# CrossPort.net
KiCad netlist of a schematic drawn in Altium Designer
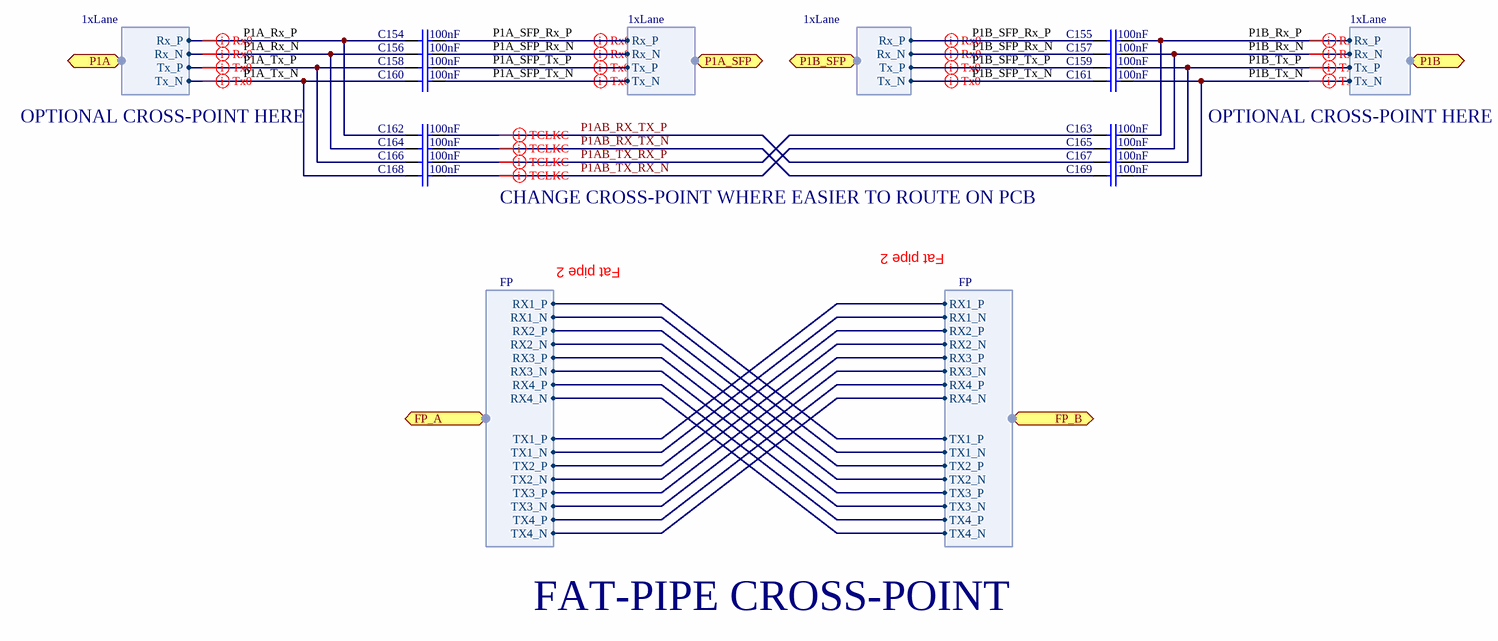
[diagram p0: CrossPort.SchDoc]

(export (version "E")
  (design (tool "Eeschema 10.0.6"))
  (components
    (comp (ref "C154")
      (value "100nF")
      (footprint "CAPC0603X33N")
      (description "Non-polarised capacitor")
      (fields
        (field (name "PART NUMBER") "CC0201_100NF_6.3V_10%_X5R")
        (field (name "VOLTAGE") "6.3V")
        (field (name "AUTHOR") "CERN DEM JLC")
      )
      (libsource (lib "Capacitors") (part "Capacitor - non polarized"))
    )
    (comp (ref "C155")
      (value "100nF")
      (footprint "CAPC0603X33N")
      (description "Non-polarised capacitor")
      (fields
        (field (name "PART NUMBER") "CC0201_100NF_6.3V_10%_X5R")
        (field (name "VOLTAGE") "6.3V")
        (field (name "AUTHOR") "CERN DEM JLC")
      )
      (libsource (lib "Capacitors") (part "Capacitor - non polarized"))
    )
    (comp (ref "C156")
      (value "100nF")
      (footprint "CAPC0603X33N")
      (description "Non-polarised capacitor")
      (fields
        (field (name "PART NUMBER") "CC0201_100NF_6.3V_10%_X5R")
        (field (name "VOLTAGE") "6.3V")
        (field (name "AUTHOR") "CERN DEM JLC")
      )
      (libsource (lib "Capacitors") (part "Capacitor - non polarized"))
    )
    (comp (ref "C157")
      (value "100nF")
      (footprint "CAPC0603X33N")
      (description "Non-polarised capacitor")
      (fields
        (field (name "PART NUMBER") "CC0201_100NF_6.3V_10%_X5R")
        (field (name "VOLTAGE") "6.3V")
        (field (name "AUTHOR") "CERN DEM JLC")
      )
      (libsource (lib "Capacitors") (part "Capacitor - non polarized"))
    )
    (comp (ref "C158")
      (value "100nF")
      (footprint "CAPC0603X33N")
      (description "Non-polarised capacitor")
      (fields
        (field (name "PART NUMBER") "CC0201_100NF_6.3V_10%_X5R")
        (field (name "VOLTAGE") "6.3V")
        (field (name "AUTHOR") "CERN DEM JLC")
      )
      (libsource (lib "Capacitors") (part "Capacitor - non polarized"))
    )
    (comp (ref "C159")
      (value "100nF")
      (footprint "CAPC0603X33N")
      (description "Non-polarised capacitor")
      (fields
        (field (name "PART NUMBER") "CC0201_100NF_6.3V_10%_X5R")
        (field (name "VOLTAGE") "6.3V")
        (field (name "AUTHOR") "CERN DEM JLC")
      )
      (libsource (lib "Capacitors") (part "Capacitor - non polarized"))
    )
    (comp (ref "C160")
      (value "100nF")
      (footprint "CAPC0603X33N")
      (description "Non-polarised capacitor")
      (fields
        (field (name "PART NUMBER") "CC0201_100NF_6.3V_10%_X5R")
        (field (name "VOLTAGE") "6.3V")
        (field (name "AUTHOR") "CERN DEM JLC")
      )
      (libsource (lib "Capacitors") (part "Capacitor - non polarized"))
    )
    (comp (ref "C161")
      (value "100nF")
      (footprint "CAPC0603X33N")
      (description "Non-polarised capacitor")
      (fields
        (field (name "PART NUMBER") "CC0201_100NF_6.3V_10%_X5R")
        (field (name "VOLTAGE") "6.3V")
        (field (name "AUTHOR") "CERN DEM JLC")
      )
      (libsource (lib "Capacitors") (part "Capacitor - non polarized"))
    )
    (comp (ref "C162")
      (value "100nF")
      (footprint "CAPC0603X33N")
      (description "Non-polarised capacitor")
      (fields
        (field (name "PART NUMBER") "CC0201_100NF_6.3V_10%_X5R")
        (field (name "VOLTAGE") "6.3V")
        (field (name "AUTHOR") "CERN DEM JLC")
      )
      (libsource (lib "Capacitors") (part "Capacitor - non polarized"))
    )
    (comp (ref "C163")
      (value "100nF")
      (footprint "CAPC0603X33N")
      (description "Non-polarised capacitor")
      (fields
        (field (name "PART NUMBER") "CC0201_100NF_6.3V_10%_X5R")
        (field (name "VOLTAGE") "6.3V")
        (field (name "AUTHOR") "CERN DEM JLC")
      )
      (libsource (lib "Capacitors") (part "Capacitor - non polarized"))
    )
    (comp (ref "C164")
      (value "100nF")
      (footprint "CAPC0603X33N")
      (description "Non-polarised capacitor")
      (fields
        (field (name "PART NUMBER") "CC0201_100NF_6.3V_10%_X5R")
        (field (name "VOLTAGE") "6.3V")
        (field (name "AUTHOR") "CERN DEM JLC")
      )
      (libsource (lib "Capacitors") (part "Capacitor - non polarized"))
    )
    (comp (ref "C165")
      (value "100nF")
      (footprint "CAPC0603X33N")
      (description "Non-polarised capacitor")
      (fields
        (field (name "PART NUMBER") "CC0201_100NF_6.3V_10%_X5R")
        (field (name "VOLTAGE") "6.3V")
        (field (name "AUTHOR") "CERN DEM JLC")
      )
      (libsource (lib "Capacitors") (part "Capacitor - non polarized"))
    )
    (comp (ref "C166")
      (value "100nF")
      (footprint "CAPC0603X33N")
      (description "Non-polarised capacitor")
      (fields
        (field (name "PART NUMBER") "CC0201_100NF_6.3V_10%_X5R")
        (field (name "VOLTAGE") "6.3V")
        (field (name "AUTHOR") "CERN DEM JLC")
      )
      (libsource (lib "Capacitors") (part "Capacitor - non polarized"))
    )
    (comp (ref "C167")
      (value "100nF")
      (footprint "CAPC0603X33N")
      (description "Non-polarised capacitor")
      (fields
        (field (name "PART NUMBER") "CC0201_100NF_6.3V_10%_X5R")
        (field (name "VOLTAGE") "6.3V")
        (field (name "AUTHOR") "CERN DEM JLC")
      )
      (libsource (lib "Capacitors") (part "Capacitor - non polarized"))
    )
    (comp (ref "C168")
      (value "100nF")
      (footprint "CAPC0603X33N")
      (description "Non-polarised capacitor")
      (fields
        (field (name "PART NUMBER") "CC0201_100NF_6.3V_10%_X5R")
        (field (name "VOLTAGE") "6.3V")
        (field (name "AUTHOR") "CERN DEM JLC")
      )
      (libsource (lib "Capacitors") (part "Capacitor - non polarized"))
    )
    (comp (ref "C169")
      (value "100nF")
      (footprint "CAPC0603X33N")
      (description "Non-polarised capacitor")
      (fields
        (field (name "PART NUMBER") "CC0201_100NF_6.3V_10%_X5R")
        (field (name "VOLTAGE") "6.3V")
        (field (name "AUTHOR") "CERN DEM JLC")
      )
      (libsource (lib "Capacitors") (part "Capacitor - non polarized"))
    )
  )
  (nets
    (net (code "3") (name "/P1AB_RX_TX_N") (class "Default")
      (node (ref "C164") (pin "1") (pinfunction "1_1") (pintype "passive"))
      (node (ref "C169") (pin "2") (pinfunction "2_2") (pintype "passive"))
    )
    (net (code "4") (name "/P1AB_RX_TX_P") (class "Default")
      (node (ref "C162") (pin "1") (pinfunction "1_1") (pintype "passive"))
      (node (ref "C167") (pin "2") (pinfunction "2_2") (pintype "passive"))
    )
    (net (code "5") (name "/P1AB_TX_RX_N") (class "Default")
      (node (ref "C165") (pin "2") (pinfunction "2_2") (pintype "passive"))
      (node (ref "C168") (pin "1") (pinfunction "1_1") (pintype "passive"))
    )
    (net (code "6") (name "/P1AB_TX_RX_P") (class "Default")
      (node (ref "C163") (pin "2") (pinfunction "2_2") (pintype "passive"))
      (node (ref "C166") (pin "1") (pinfunction "1_1") (pintype "passive"))
    )
    (net (code "7") (name "/P1A_Rx_N") (class "Default")
      (node (ref "C156") (pin "2") (pinfunction "2_2") (pintype "passive"))
      (node (ref "C164") (pin "2") (pinfunction "2_2") (pintype "passive"))
    )
    (net (code "8") (name "/P1A_Rx_P") (class "Default")
      (node (ref "C154") (pin "2") (pinfunction "2_2") (pintype "passive"))
      (node (ref "C162") (pin "2") (pinfunction "2_2") (pintype "passive"))
    )
    (net (code "9") (name "/P1A_SFP_Rx_N") (class "Default")
      (node (ref "C156") (pin "1") (pinfunction "1_1") (pintype "passive"))
    )
    (net (code "10") (name "/P1A_SFP_Rx_P") (class "Default")
      (node (ref "C154") (pin "1") (pinfunction "1_1") (pintype "passive"))
    )
    (net (code "11") (name "/P1A_SFP_Tx_N") (class "Default")
      (node (ref "C160") (pin "1") (pinfunction "1_1") (pintype "passive"))
    )
    (net (code "12") (name "/P1A_SFP_Tx_P") (class "Default")
      (node (ref "C158") (pin "1") (pinfunction "1_1") (pintype "passive"))
    )
    (net (code "13") (name "/P1A_Tx_N") (class "Default")
      (node (ref "C160") (pin "2") (pinfunction "2_2") (pintype "passive"))
      (node (ref "C168") (pin "2") (pinfunction "2_2") (pintype "passive"))
    )
    (net (code "14") (name "/P1A_Tx_P") (class "Default")
      (node (ref "C158") (pin "2") (pinfunction "2_2") (pintype "passive"))
      (node (ref "C166") (pin "2") (pinfunction "2_2") (pintype "passive"))
    )
    (net (code "15") (name "/P1B_Rx_N") (class "Default")
      (node (ref "C157") (pin "1") (pinfunction "1_1") (pintype "passive"))
      (node (ref "C165") (pin "1") (pinfunction "1_1") (pintype "passive"))
    )
    (net (code "16") (name "/P1B_Rx_P") (class "Default")
      (node (ref "C155") (pin "1") (pinfunction "1_1") (pintype "passive"))
      (node (ref "C163") (pin "1") (pinfunction "1_1") (pintype "passive"))
    )
    (net (code "17") (name "/P1B_SFP_Rx_N") (class "Default")
      (node (ref "C157") (pin "2") (pinfunction "2_2") (pintype "passive"))
    )
    (net (code "18") (name "/P1B_SFP_Rx_P") (class "Default")
      (node (ref "C155") (pin "2") (pinfunction "2_2") (pintype "passive"))
    )
    (net (code "19") (name "/P1B_SFP_Tx_N") (class "Default")
      (node (ref "C161") (pin "2") (pinfunction "2_2") (pintype "passive"))
    )
    (net (code "20") (name "/P1B_SFP_Tx_P") (class "Default")
      (node (ref "C159") (pin "2") (pinfunction "2_2") (pintype "passive"))
    )
    (net (code "21") (name "/P1B_Tx_N") (class "Default")
      (node (ref "C161") (pin "1") (pinfunction "1_1") (pintype "passive"))
      (node (ref "C169") (pin "1") (pinfunction "1_1") (pintype "passive"))
    )
    (net (code "22") (name "/P1B_Tx_P") (class "Default")
      (node (ref "C159") (pin "1") (pinfunction "1_1") (pintype "passive"))
      (node (ref "C167") (pin "1") (pinfunction "1_1") (pintype "passive"))
    )
  )
)
